# H2AR30.net
KiCad netlist of a schematic drawn in EAGLE
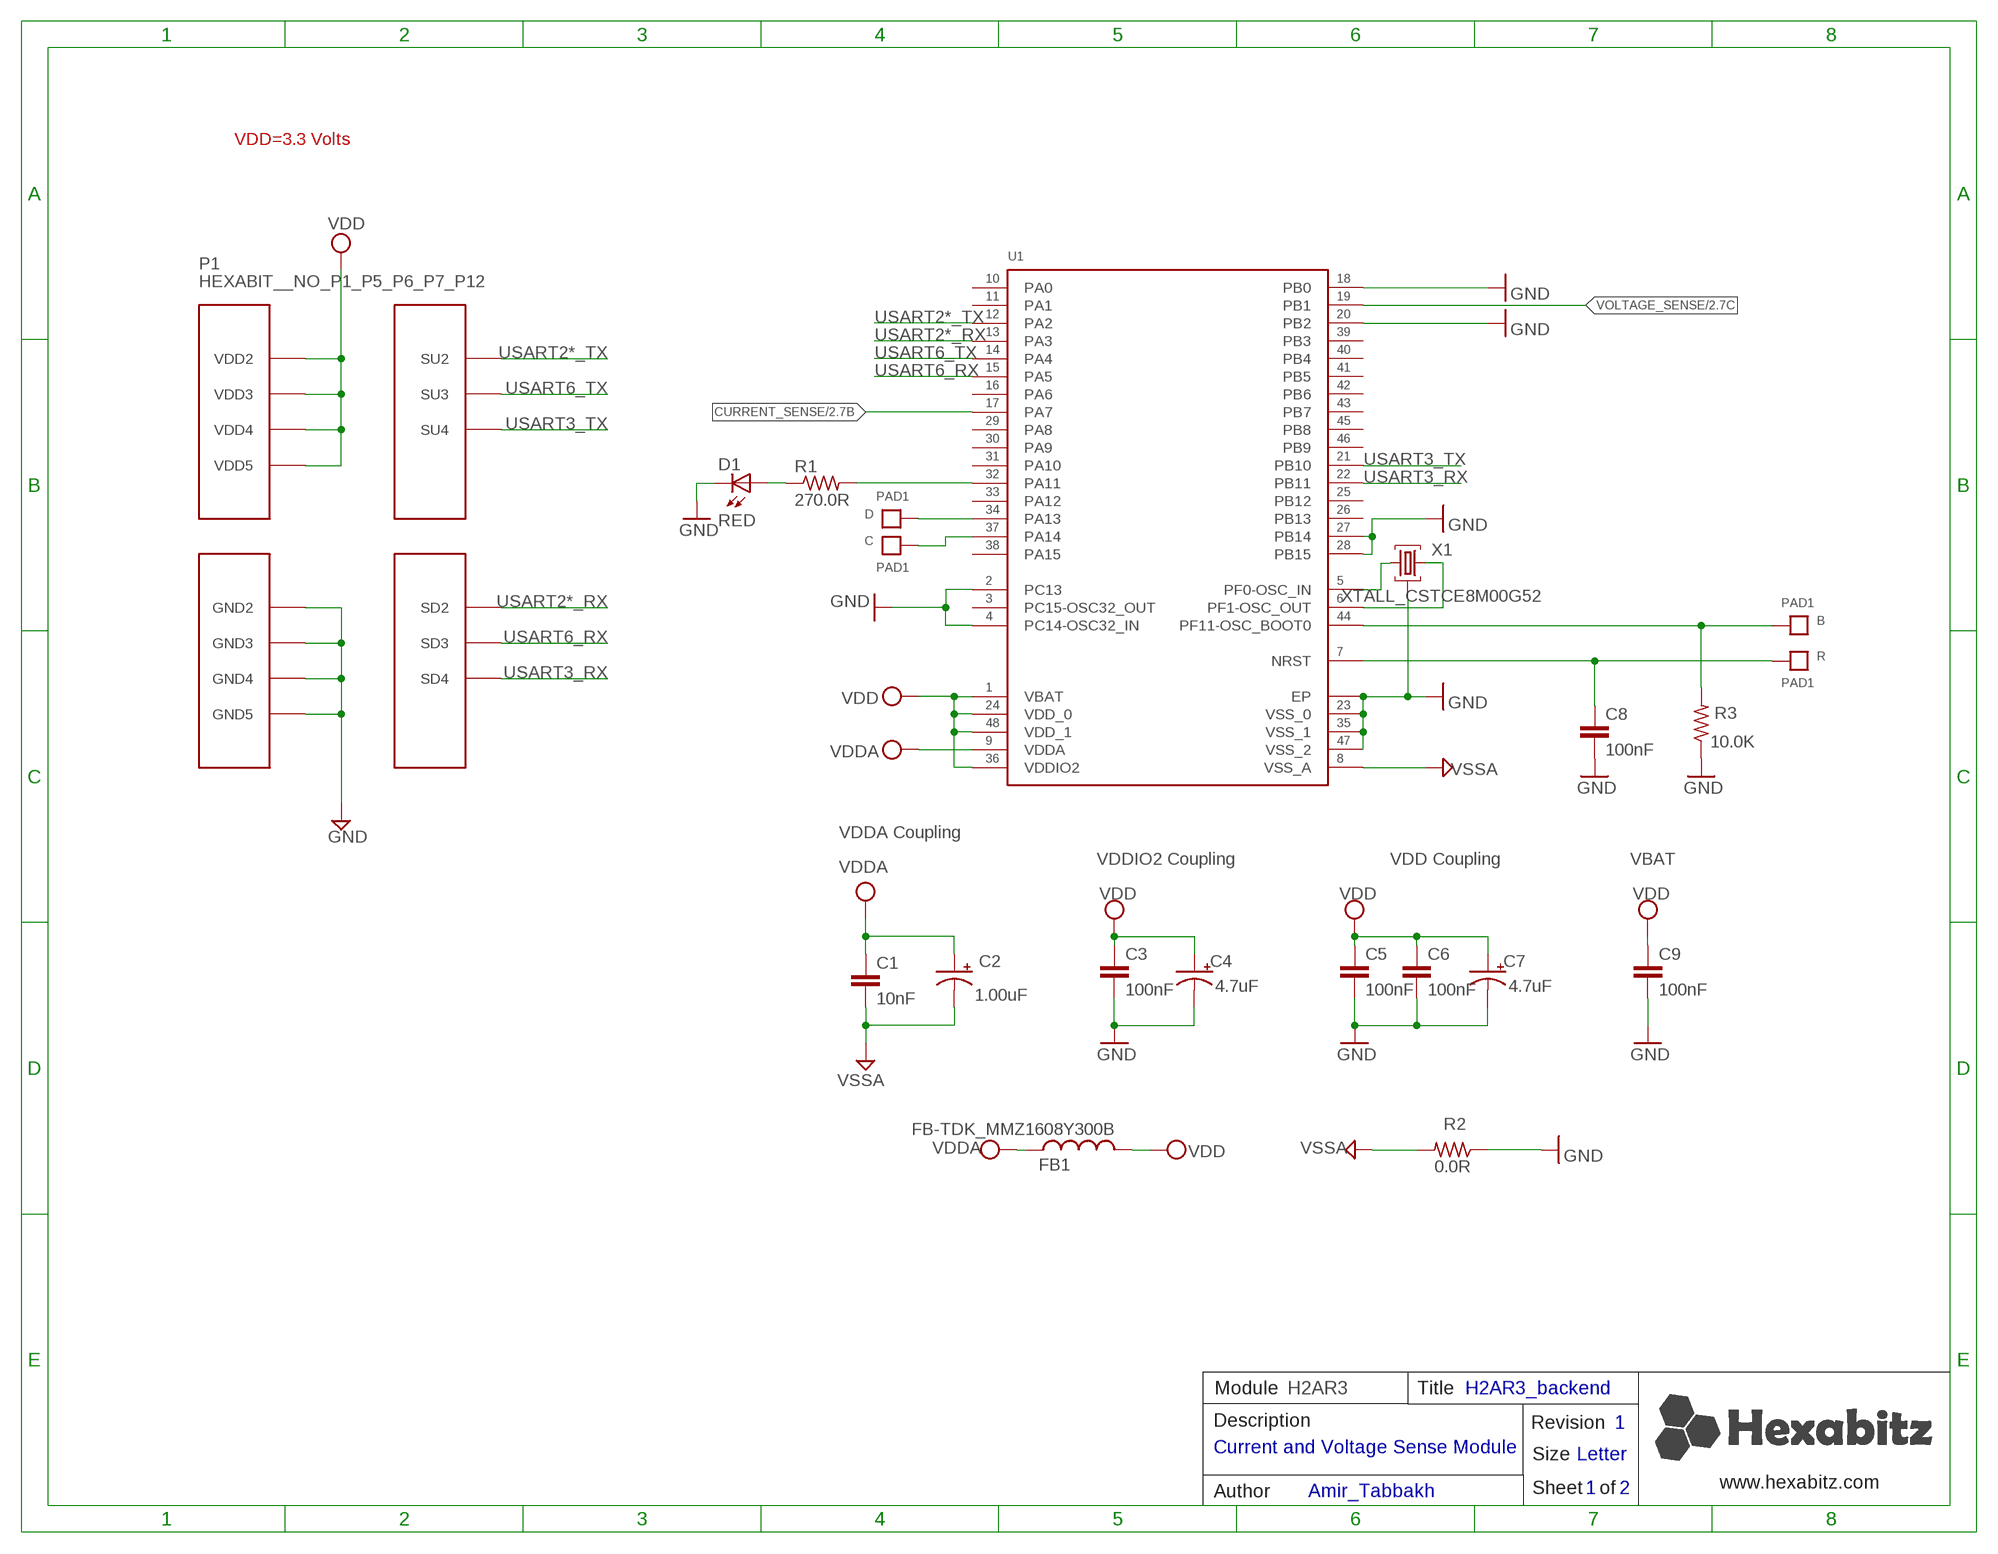
[diagram p0: schematic, sheet 1]
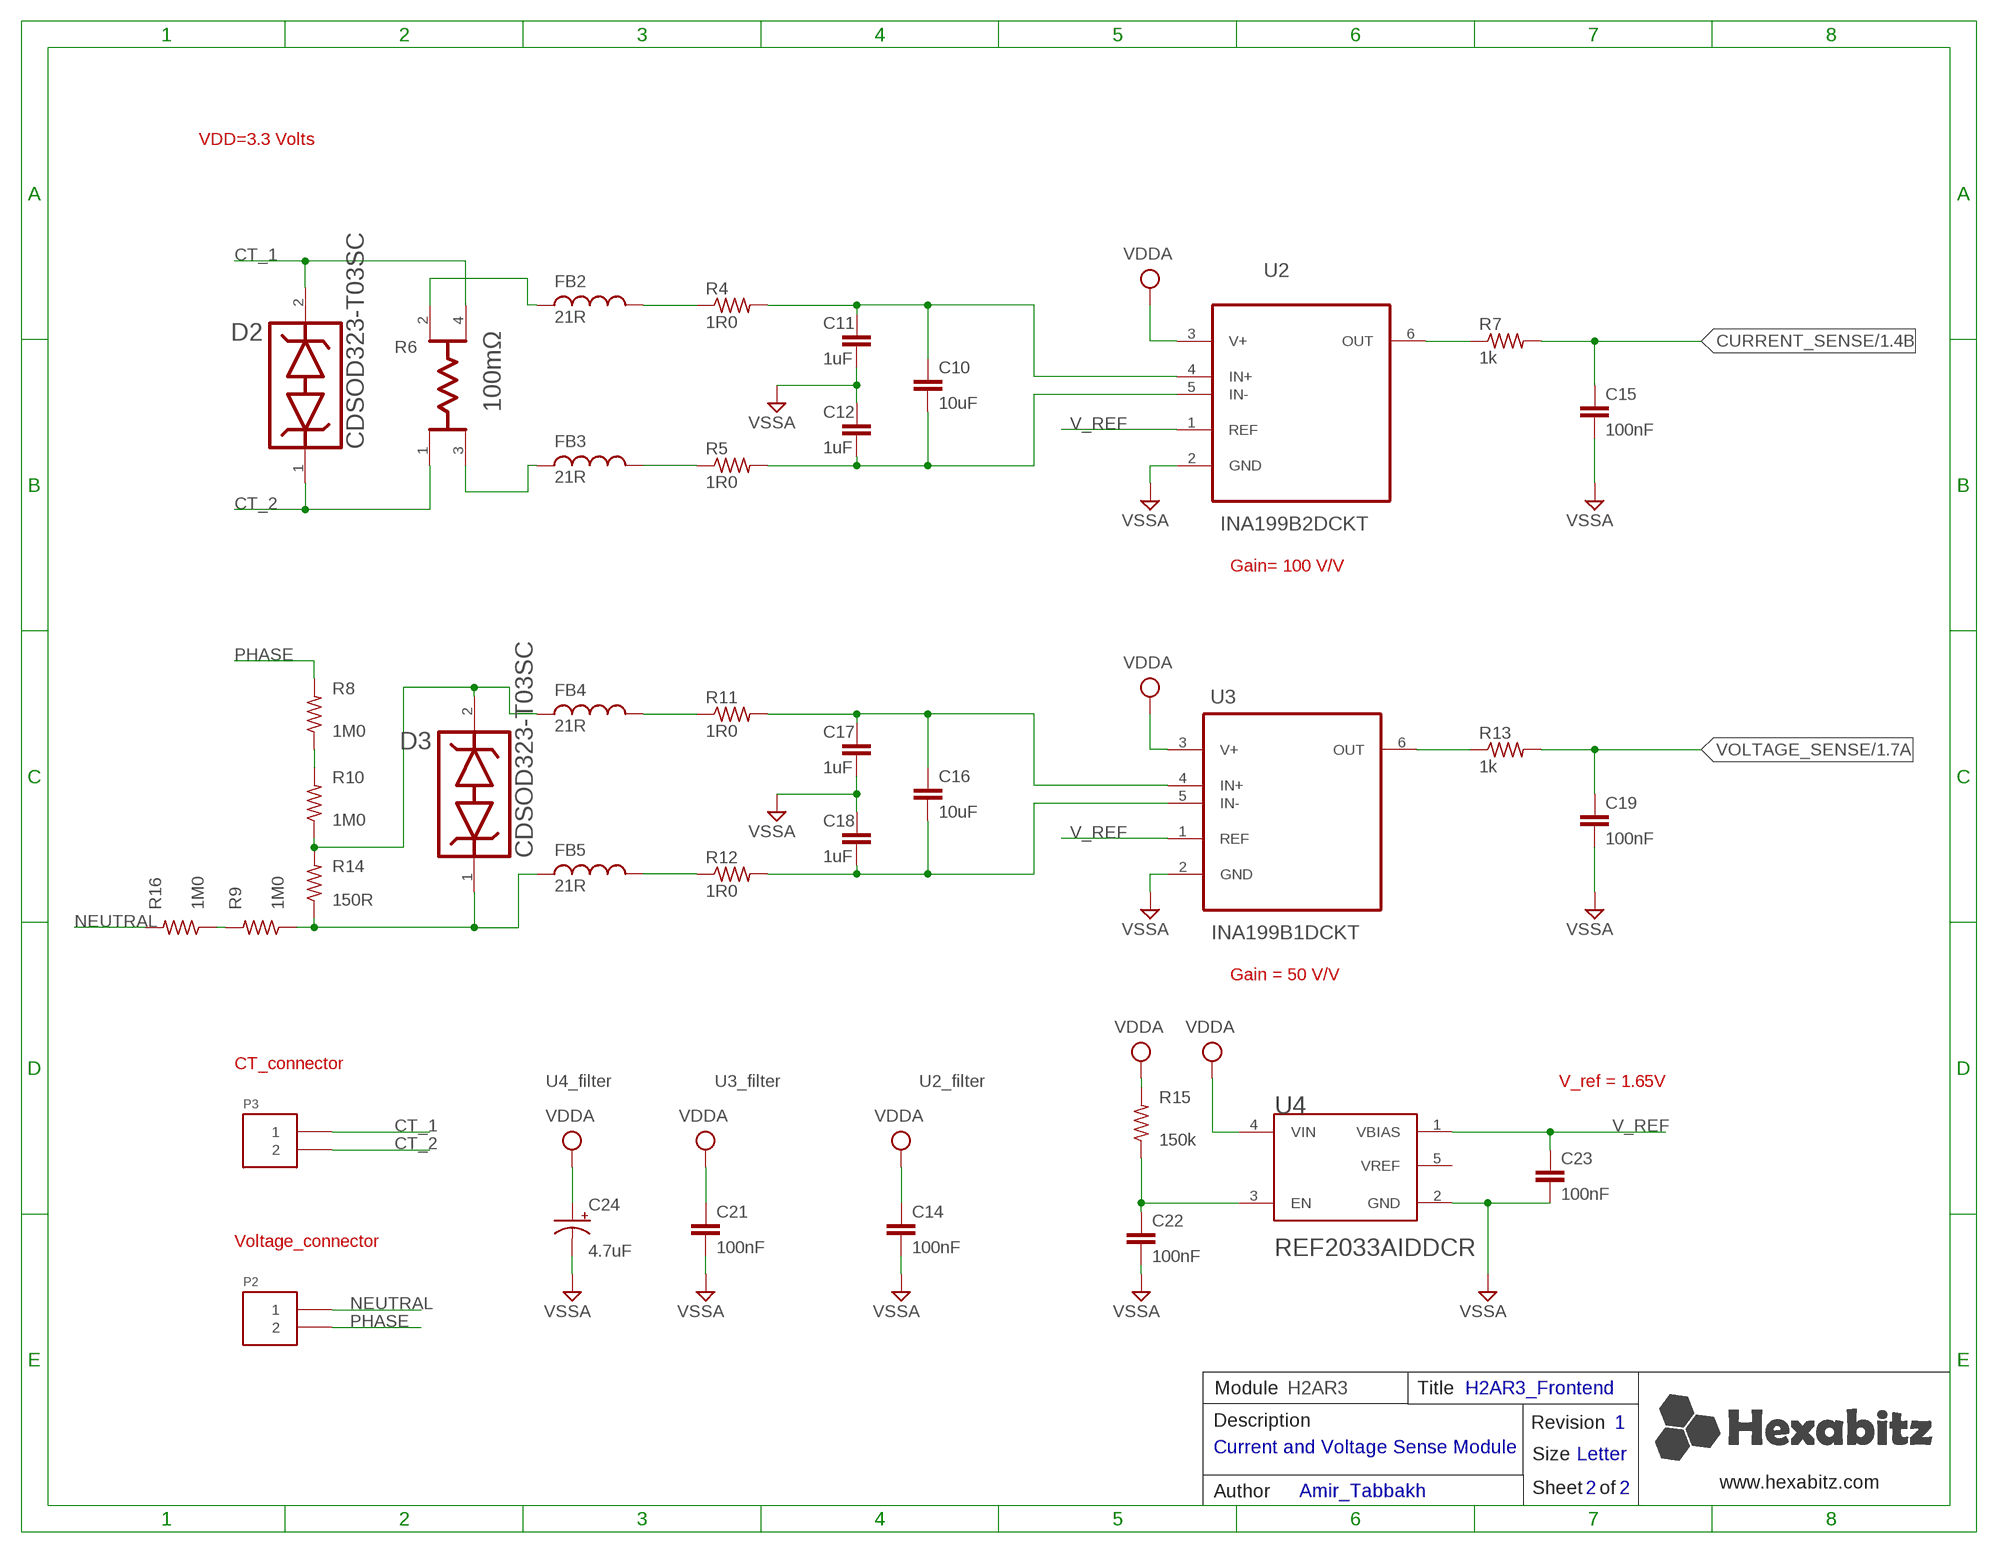
[diagram p1: schematic, sheet 2]

(export (version "E")
  (design (tool "Eeschema 10.0.6"))
  (components
    (comp (ref "C10")
      (value "10uF")
      (footprint "eagle-import:C-0603")
      (fields
        (field (name "CAPACITANCE") "10uF")
        (field (name "MFN") "KEMET")
        (field (name "MPN") "C0603C106M9PACTU")
        (field (name "OCTOPART_URL") "https://octopart.com/c0603c106m9pactu-kemet-8375727?r=sp")
        (field (name "VOLTAGE_RATING") "6.3v")
      )
      (libsource (lib "eagle-import") (part "C-0603"))
    )
    (comp (ref "C11")
      (value "1uF")
      (footprint "eagle-import:C-0603")
      (fields
        (field (name "CAPACITANCE") "1uF")
        (field (name "MFN") "KEMET")
        (field (name "MPN") "C0603C105K8RACTU")
        (field (name "OCTOPART_URL") "https://octopart.com/c0603c105k8ractu-kemet-12595642?r=sp")
        (field (name "TOLERANCE") "10%")
        (field (name "VOLTAGE_RATING") "10v")
      )
      (libsource (lib "eagle-import") (part "C-0603"))
    )
    (comp (ref "C12")
      (value "1uF")
      (footprint "eagle-import:C-0603")
      (fields
        (field (name "CAPACITANCE") "1uF")
        (field (name "MFN") "KEMET")
        (field (name "MPN") "C0603C105K8RACTU")
        (field (name "OCTOPART_URL") "https://octopart.com/c0603c105k8ractu-kemet-12595642?r=sp")
        (field (name "TOLERANCE") "10%")
        (field (name "VOLTAGE_RATING") "10v")
      )
      (libsource (lib "eagle-import") (part "C-0603"))
    )
    (comp (ref "C14")
      (value "100nF")
      (footprint "eagle-import:C-0603")
      (fields
        (field (name "CAPACITANCE") "100nF")
        (field (name "MFN") "KEMET")
        (field (name "MPN") "C0603C104K8RACTU")
        (field (name "OCTOPART_URL") "https://octopart.com/c0603c104k8ractu-kemet-145075?r=sp&s=9bS9ASSwSEqMCE9KBEQZ0g")
        (field (name "TOLERANCE") "10%")
        (field (name "VOLTAGE_RATING") "10V")
      )
      (libsource (lib "eagle-import") (part "C-0603"))
    )
    (comp (ref "C15")
      (value "100nF")
      (footprint "eagle-import:C-0603")
      (fields
        (field (name "CAPACITANCE") "100nF")
        (field (name "MFN") "KEMET")
        (field (name "MPN") "C0603C104K8RACTU")
        (field (name "OCTOPART_URL") "https://octopart.com/c0603c104k8ractu-kemet-145075?r=sp&s=9bS9ASSwSEqMCE9KBEQZ0g")
        (field (name "TOLERANCE") "10%")
        (field (name "VOLTAGE_RATING") "10V")
      )
      (libsource (lib "eagle-import") (part "C-0603"))
    )
    (comp (ref "C16")
      (value "10uF")
      (footprint "eagle-import:C-0603")
      (fields
        (field (name "CAPACITANCE") "10uF")
        (field (name "MFN") "KEMET")
        (field (name "MPN") "C0603C106M9PACTU")
        (field (name "OCTOPART_URL") "https://octopart.com/c0603c106m9pactu-kemet-8375727?r=sp")
        (field (name "TOLERANCE") "20%")
        (field (name "VOLTAGE_RATING") "6.3V")
      )
      (libsource (lib "eagle-import") (part "C-0603"))
    )
    (comp (ref "C17")
      (value "1uF")
      (footprint "eagle-import:C-0603")
      (fields
        (field (name "CAPACITANCE") "1uF")
        (field (name "MFN") "KEMET")
        (field (name "MPN") "C0603C105K8RACTU")
        (field (name "OCTOPART_URL") "https://octopart.com/c0603c105k8ractu-kemet-12595642?r=sp")
        (field (name "TOLERANCE") "10%")
        (field (name "VOLTAGE_RATING") "10v")
      )
      (libsource (lib "eagle-import") (part "C-0603"))
    )
    (comp (ref "C18")
      (value "1uF")
      (footprint "eagle-import:C-0603")
      (fields
        (field (name "CAPACITANCE") "1uF")
        (field (name "MFN") "KEMET")
        (field (name "MPN") "C0603C105K8RACTU")
        (field (name "OCTOPART_URL") "https://octopart.com/c0603c105k8ractu-kemet-12595642?r=sp")
        (field (name "TOLERANCE") "10%")
        (field (name "VOLTAGE_RATING") "10v")
      )
      (libsource (lib "eagle-import") (part "C-0603"))
    )
    (comp (ref "C19")
      (value "100nF")
      (footprint "eagle-import:C-0603")
      (fields
        (field (name "CAPACITANCE") "100nF")
        (field (name "MFN") "KEMET")
        (field (name "MPN") "C0603C104K8RACTU")
        (field (name "OCTOPART_URL") "https://octopart.com/c0603c104k8ractu-kemet-145075?r=sp&s=9bS9ASSwSEqMCE9KBEQZ0g")
        (field (name "TOLERANCE") "10%")
        (field (name "VOLTAGE_RATING") "10V")
      )
      (libsource (lib "eagle-import") (part "C-0603"))
    )
    (comp (ref "C21")
      (value "100nF")
      (footprint "eagle-import:C-0603")
      (fields
        (field (name "CAPACITANCE") "100nF")
        (field (name "MFN") "KEMET")
        (field (name "MPN") "C0603C104K8RACTU")
        (field (name "OCTOPART_URL") "https://octopart.com/c0603c104k8ractu-kemet-145075?r=sp&s=9bS9ASSwSEqMCE9KBEQZ0g")
        (field (name "TOLERANCE") "10%")
        (field (name "VOLTAGE_RATING") "10V")
      )
      (libsource (lib "eagle-import") (part "C-0603"))
    )
    (comp (ref "C22")
      (value "100nF")
      (footprint "eagle-import:C-0603")
      (fields
        (field (name "CAPACITANCE") "100nF")
        (field (name "MFN") "KEMET")
        (field (name "MPN") "C0603C104K8RACTU")
        (field (name "OCTOPART_URL") "https://octopart.com/c0603c104k8ractu-kemet-145075?r=sp&s=9bS9ASSwSEqMCE9KBEQZ0g")
        (field (name "TOLERANCE") "10%")
        (field (name "VOLTAGE_RATING") "10V")
      )
      (libsource (lib "eagle-import") (part "C-0603"))
    )
    (comp (ref "C23")
      (value "100nF")
      (footprint "eagle-import:C-0603")
      (fields
        (field (name "CAPACITANCE") "100nF")
        (field (name "MFN") "KEMET")
        (field (name "MPN") "C0603C104K8RACTU")
        (field (name "OCTOPART_URL") "https://octopart.com/c0603c104k8ractu-kemet-145075?r=sp&s=9bS9ASSwSEqMCE9KBEQZ0g")
        (field (name "TOLERANCE") "10%")
        (field (name "VOLTAGE_RATING") "10V")
      )
      (libsource (lib "eagle-import") (part "C-0603"))
    )
    (comp (ref "C24")
      (value "4.7uF")
      (footprint "eagle-import:C-0805-POL")
      (fields
        (field (name "CAPACITANCE") "4.7uF")
        (field (name "MFN") "Murata")
        (field (name "MPN") "GRM21BC81E475KA12L")
        (field (name "OCTOPART_URL") "https://octopart.com/grm21bc81e475ka12l-murata-10331911?r=sp&s=RY3qZSD8T6mG6TC9CHI5qQ")
        (field (name "TOLERANCE") "10%")
        (field (name "VOLTAGE_RATING") "25V")
      )
      (libsource (lib "eagle-import") (part "C-0805-POL"))
    )
    (comp (ref "D2")
      (value "BOURNS_CDSOD323-T03SCBOURNS_CDSOD323-T03SC_0_0")
      (footprint "eagle-import:BOURNS_CDSOD323-T03SC_0")
      (fields (field (name "MPN") "CDSOD323-T03SC"))
      (libsource (lib "eagle-import") (part "BOURNS_CDSOD323-T03SCBOURNS_CDSOD323-T03SC_0_0"))
    )
    (comp (ref "D3")
      (value "BOURNS_CDSOD323-T03SCBOURNS_CDSOD323-T03SC_0_0")
      (footprint "eagle-import:BOURNS_CDSOD323-T03SC_0")
      (fields (field (name "MPN") "CDSOD323-T03SC"))
      (libsource (lib "eagle-import") (part "BOURNS_CDSOD323-T03SCBOURNS_CDSOD323-T03SC_0_0"))
    )
    (comp (ref "FB2")
      (value "21R")
      (footprint "eagle-import:FB-0805")
      (fields
        (field (name "MFN") "Taiyo Yuden")
        (field (name "MPN") "FBMJ2125HM210NT")
        (field (name "OCTOPART_URL") "https://octopart.com/fbmj2125hm210nt-taiyo+yuden-368424?r=sp")
      )
      (libsource (lib "eagle-import") (part "FB-0805"))
    )
    (comp (ref "FB3")
      (value "21R")
      (footprint "eagle-import:FB-0805")
      (fields
        (field (name "MFN") "Taiyo Yuden")
        (field (name "MPN") "FBMJ2125HM210NT")
        (field (name "OCTOPART_URL") "https://octopart.com/fbmj2125hm210nt-taiyo+yuden-368424?r=sp")
      )
      (libsource (lib "eagle-import") (part "FB-0805"))
    )
    (comp (ref "FB4")
      (value "21R")
      (footprint "eagle-import:FB-0805")
      (fields
        (field (name "MFN") "Taiyo Yuden")
        (field (name "MPN") "FBMJ2125HM210NT")
        (field (name "OCTOPART_URL") "https://octopart.com/fbmj2125hm210nt-taiyo+yuden-368424?r=sp")
      )
      (libsource (lib "eagle-import") (part "FB-0805"))
    )
    (comp (ref "FB5")
      (value "21R")
      (footprint "eagle-import:FB-0805")
      (fields
        (field (name "MFN") "Taiyo Yuden")
        (field (name "MPN") "FBMJ2125HM210NT")
        (field (name "OCTOPART_URL") "https://octopart.com/fbmj2125hm210nt-taiyo+yuden-368424?r=sp")
      )
      (libsource (lib "eagle-import") (part "FB-0805"))
    )
    (comp (ref "P2")
      (value "1546111-2")
      (footprint "eagle-import:1546111-2")
      (libsource (lib "eagle-import") (part "1546111-2"))
    )
    (comp (ref "P3")
      (value "1546111-2")
      (footprint "eagle-import:1546111-2")
      (libsource (lib "eagle-import") (part "1546111-2"))
    )
    (comp (ref "R4")
      (value "1R0")
      (footprint "eagle-import:R-0603")
      (fields
        (field (name "MFN") "Vishay")
        (field (name "MPN") "CRCW06031R00FKEA")
        (field (name "OCTOPART_URL") "https://octopart.com/crcw06031r00fkea-vishay-39713722?r=sp&s=biXSlGylTBiwPOCcABx_kA")
        (field (name "RESISTANCE") "1")
        (field (name "TOLERANCE") "1%")
      )
      (libsource (lib "eagle-import") (part "R-0603"))
    )
    (comp (ref "R5")
      (value "1R0")
      (footprint "eagle-import:R-0603")
      (fields
        (field (name "MFN") "Vishay")
        (field (name "MPN") "CRCW06031R00FKEA")
        (field (name "OCTOPART_URL") "https://octopart.com/crcw06031r00fkea-vishay-39713722?r=sp&s=biXSlGylTBiwPOCcABx_kA")
        (field (name "RESISTANCE") "1")
        (field (name "TOLERANCE") "1%")
      )
      (libsource (lib "eagle-import") (part "R-0603"))
    )
    (comp (ref "R6")
      (value "VISHAY_Y14870R10000B9RVISHAY_Y14870R10000B9R_0_0")
      (footprint "eagle-import:VISHAY_Y14870R10000B9R_0")
      (fields (field (name "MPN") "Y14870R10000B9R"))
      (libsource (lib "eagle-import") (part "VISHAY_Y14870R10000B9RVISHAY_Y14870R10000B9R_0_0"))
    )
    (comp (ref "R7")
      (value "1k")
      (footprint "eagle-import:R-0603")
      (fields
        (field (name "MFN") "Yageo")
        (field (name "MPN") "RC0603JR-071KL")
        (field (name "OCTOPART_URL") "https://octopart.com/rc0603jr-071kl-yageo-55402888?r=sp")
        (field (name "RESISTANCE") "1K")
        (field (name "TOLERANCE") "5%")
      )
      (libsource (lib "eagle-import") (part "R-0603"))
    )
    (comp (ref "R8")
      (value "1M0")
      (footprint "eagle-import:R1206")
      (fields
        (field (name "MPN") "RNCF2512BTE1M10")
        (field (name "MFN") "Yageo")
        (field (name "MPN_1") "RT1206BRD071ML")
        (field (name "OCTOPART_URL") "https://octopart.com/rt1206brd071ml-yageo-1262221?r=sp")
      )
      (libsource (lib "eagle-import") (part "R_1206R1206"))
    )
    (comp (ref "R9")
      (value "1M0")
      (footprint "eagle-import:R1206")
      (fields
        (field (name "MPN") "RNCF2512BTE1M10")
        (field (name "MFN") "Yageo")
        (field (name "MPN_1") "RT1206BRD071ML")
        (field (name "OCTOPART_URL") "https://octopart.com/rt1206brd071ml-yageo-1262221?r=sp")
      )
      (libsource (lib "eagle-import") (part "R_1206R1206"))
    )
    (comp (ref "R10")
      (value "1M0")
      (footprint "eagle-import:R1206")
      (fields
        (field (name "MPN") "RNCF2512BTE1M10")
        (field (name "MFN") "Yageo")
        (field (name "MPN_1") "RT1206BRD071ML")
        (field (name "OCTOPART_URL") "https://octopart.com/rt1206brd071ml-yageo-1262221?r=sp")
      )
      (libsource (lib "eagle-import") (part "R_1206R1206"))
    )
    (comp (ref "R11")
      (value "1R0")
      (footprint "eagle-import:R-0603")
      (fields
        (field (name "MFN") "Vishay")
        (field (name "MPN") "CRCW06031R00FKEA")
        (field (name "OCTOPART_URL") "https://octopart.com/crcw06031r00fkea-vishay-39713722?r=sp&s=biXSlGylTBiwPOCcABx_kA")
        (field (name "RESISTANCE") "1")
        (field (name "TOLERANCE") "1%")
      )
      (libsource (lib "eagle-import") (part "R-0603"))
    )
    (comp (ref "R12")
      (value "1R0")
      (footprint "eagle-import:R-0603")
      (fields
        (field (name "MFN") "Vishay")
        (field (name "MPN") "CRCW06031R00FKEA")
        (field (name "OCTOPART_URL") "https://octopart.com/crcw06031r00fkea-vishay-39713722?r=sp&s=biXSlGylTBiwPOCcABx_kA")
        (field (name "RESISTANCE") "1")
        (field (name "TOLERANCE") "1%")
      )
      (libsource (lib "eagle-import") (part "R-0603"))
    )
    (comp (ref "R13")
      (value "1k")
      (footprint "eagle-import:R-0603")
      (fields
        (field (name "MFN") "Yageo")
        (field (name "MPN") "RC0603JR-071KL")
        (field (name "OCTOPART_URL") "https://octopart.com/rc0603jr-071kl-yageo-55402888?r=sp")
        (field (name "RESISTANCE") "1K")
        (field (name "TOLERANCE") "5%")
      )
      (libsource (lib "eagle-import") (part "R-0603"))
    )
    (comp (ref "R14")
      (value "150R")
      (footprint "eagle-import:R1206")
      (fields
        (field (name "MPN") "RNCF2512BTE1M10")
        (field (name "MFN") "Panasonic")
        (field (name "MPN_1") "ERA-8AEB151V")
        (field (name "OCTOPART_URL") "https://octopart.com/era-8aeb151v-panasonic-55477439?r=sp")
      )
      (libsource (lib "eagle-import") (part "R_1206R1206"))
    )
    (comp (ref "R15")
      (value "150k")
      (footprint "eagle-import:R-0603")
      (fields
        (field (name "MFN") "Vishay")
        (field (name "MPN") "CRCW0603150KFKEA")
        (field (name "OCTOPART_URL") "https://octopart.com/crcw0603150kfkea-vishay-39455816?r=sp")
        (field (name "RESISTANCE") "150K")
        (field (name "TOLERANCE") "1%")
      )
      (libsource (lib "eagle-import") (part "R-0603"))
    )
    (comp (ref "R16")
      (value "1M0")
      (footprint "eagle-import:R1206")
      (fields
        (field (name "MPN") "RNCF2512BTE1M10")
        (field (name "MFN") "Yageo")
        (field (name "MPN_1") "RT1206BRD071ML")
        (field (name "OCTOPART_URL") "https://octopart.com/rt1206brd071ml-yageo-1262221?r=sp")
      )
      (libsource (lib "eagle-import") (part "R_1206R1206"))
    )
    (comp (ref "U2")
      (value "INA199B2DCKT")
      (footprint "eagle-import:SOT65P210X110-6N")
      (libsource (lib "eagle-import") (part "INA199B2DCKT"))
    )
    (comp (ref "U3")
      (value "INA199B1DCKT")
      (footprint "eagle-import:SOT65P210X110-6N")
      (libsource (lib "eagle-import") (part "INA199B1DCKT"))
    )
    (comp (ref "U4")
      (value "TEXAS_INSTRUMENTS_REF2033AIDDCRTEXAS_INSTRUMENTS_REF2033AIDDCR_0_2")
      (footprint "eagle-import:TEXAS_INSTRUMENTS_REF2033AIDDCR_2")
      (fields (field (name "MPN") "REF2033AIDDCR"))
      (libsource (lib "eagle-import") (part "TEXAS_INSTRUMENTS_REF2033AIDDCRTEXAS_INSTRUMENTS_REF2033AIDDCR_0_2"))
    )
    (comp (ref "B")
      (value "PAD1")
      (footprint "eagle-import:PAD1")
      (libsource (lib "eagle-import") (part "PAD1"))
    )
    (comp (ref "C")
      (value "PAD1")
      (footprint "eagle-import:PAD1")
      (libsource (lib "eagle-import") (part "PAD1"))
    )
    (comp (ref "C1")
      (value "10nF")
      (footprint "eagle-import:C-0603")
      (fields
        (field (name "CAPACITANCE") "10nF")
        (field (name "MFN") "KEMET")
        (field (name "MPN") "C0603C103K5RACTU")
        (field (name "OCTOPART_URL") "https://octopart.com/c0603c103k5ractu-kemet-133094?r=sp&s=R_iPBxLnSmGqhkU2rIMFpg")
        (field (name "TOLERANCE") "10%")
        (field (name "VOLTAGE_RATING") "50V")
      )
      (libsource (lib "eagle-import") (part "C-0603"))
    )
    (comp (ref "C2")
      (value "1.00uF")
      (footprint "eagle-import:C-0805-POL")
      (fields
        (field (name "CAPACITANCE") "1.00uF")
        (field (name "MFN") "Yageo")
        (field (name "MPN") "CC0805KKX7R7BB105")
        (field (name "OCTOPART_URL") "https://octopart.com/cc0805kkx7r7bb105-yageo-8376555?r=sp&s=YKl1wwtkROau_X5nniH2ig")
        (field (name "TOLERANCE") "10%")
        (field (name "VOLTAGE_RATING") "16V")
      )
      (libsource (lib "eagle-import") (part "C-0805-POL"))
    )
    (comp (ref "C3")
      (value "100nF")
      (footprint "eagle-import:C-0603")
      (fields
        (field (name "CAPACITANCE") "100nF")
        (field (name "MFN") "KEMET")
        (field (name "MPN") "C0603C104K8RACTU")
        (field (name "OCTOPART_URL") "https://octopart.com/c0603c104k8ractu-kemet-145075?r=sp&s=9bS9ASSwSEqMCE9KBEQZ0g")
        (field (name "TOLERANCE") "10%")
        (field (name "VOLTAGE_RATING") "10V")
      )
      (libsource (lib "eagle-import") (part "C-0603"))
    )
    (comp (ref "C4")
      (value "4.7uF")
      (footprint "eagle-import:C-0805-POL")
      (fields
        (field (name "CAPACITANCE") "4.7uF")
        (field (name "MFN") "Murata")
        (field (name "MPN") "GRM21BC81E475KA12L")
        (field (name "OCTOPART_URL") "https://octopart.com/grm21bc81e475ka12l-murata-10331911?r=sp&s=RY3qZSD8T6mG6TC9CHI5qQ")
        (field (name "TOLERANCE") "10%")
        (field (name "VOLTAGE_RATING") "25V")
      )
      (libsource (lib "eagle-import") (part "C-0805-POL"))
    )
    (comp (ref "C5")
      (value "100nF")
      (footprint "eagle-import:C-0603")
      (fields
        (field (name "CAPACITANCE") "100nF")
        (field (name "MFN") "KEMET")
        (field (name "MPN") "C0603C104K8RACTU")
        (field (name "OCTOPART_URL") "https://octopart.com/c0603c104k8ractu-kemet-145075?r=sp&s=9bS9ASSwSEqMCE9KBEQZ0g")
        (field (name "TOLERANCE") "10%")
        (field (name "VOLTAGE_RATING") "10")
      )
      (libsource (lib "eagle-import") (part "C-0603"))
    )
    (comp (ref "C6")
      (value "100nF")
      (footprint "eagle-import:C-0603")
      (fields
        (field (name "CAPACITANCE") "100nF")
        (field (name "MFN") "KEMET")
        (field (name "MPN") "C0603C104K8RACTU")
        (field (name "OCTOPART_URL") "https://octopart.com/c0603c104k8ractu-kemet-145075?r=sp&s=9bS9ASSwSEqMCE9KBEQZ0g")
        (field (name "TOLERANCE") "10%")
        (field (name "VOLTAGE_RATING") "10V")
      )
      (libsource (lib "eagle-import") (part "C-0603"))
    )
    (comp (ref "C7")
      (value "4.7uF")
      (footprint "eagle-import:C-0805-POL")
      (fields
        (field (name "CAPACITANCE") "4.7uF")
        (field (name "MFN") "Murata")
        (field (name "MPN") "GRM21BC81E475KA12L")
        (field (name "OCTOPART_URL") "https://octopart.com/grm21bc81e475ka12l-murata-10331911?r=sp&s=RY3qZSD8T6mG6TC9CHI5qQ")
        (field (name "TOLERANCE") "10%")
        (field (name "VOLTAGE_RATING") "25V")
      )
      (libsource (lib "eagle-import") (part "C-0805-POL"))
    )
    (comp (ref "C8")
      (value "100nF")
      (footprint "eagle-import:C-0603")
      (fields
        (field (name "CAPACITANCE") "100nF")
        (field (name "MFN") "KEMET")
        (field (name "MPN") "C0603C104K8RACTU")
        (field (name "OCTOPART_URL") "https://octopart.com/c0603c104k8ractu-kemet-145075?r=sp&s=9bS9ASSwSEqMCE9KBEQZ0g")
        (field (name "TOLERANCE") "10%")
        (field (name "VOLTAGE_RATING") "10V")
      )
      (libsource (lib "eagle-import") (part "C-0603"))
    )
    (comp (ref "C9")
      (value "100nF")
      (footprint "eagle-import:C-0603")
      (fields
        (field (name "CAPACITANCE") "100nF")
        (field (name "MFN") "KEMET")
        (field (name "MPN") "C0603C104K8RACTU")
        (field (name "OCTOPART_URL") "https://octopart.com/c0603c104k8ractu-kemet-145075?r=sp&s=9bS9ASSwSEqMCE9KBEQZ0g")
        (field (name "TOLERANCE") "10V")
        (field (name "VOLTAGE_RATING") "10%")
      )
      (libsource (lib "eagle-import") (part "C-0603"))
    )
    (comp (ref "D")
      (value "PAD1")
      (footprint "eagle-import:PAD1")
      (libsource (lib "eagle-import") (part "PAD1"))
    )
    (comp (ref "D1")
      (value "RED")
      (footprint "eagle-import:VLMS1300-GS08")
      (fields
        (field (name "MPN") "VLMS1300-GS08")
        (field (name "MFN") "Vishay")
        (field (name "MPN_1") "VLMS1300-GS08")
        (field (name "OCTOPART_URL") "https://octopart.com/vlms1300-gs08-vishay-21709201?r=sp&s=_gcP4_q8T1SC6PJQPTQ9yA")
      )
      (libsource (lib "eagle-import") (part "VLMS1300-GS08"))
    )
    (comp (ref "FB1")
      (value "FB-TDK_MMZ1608Y300B")
      (footprint "eagle-import:FB-TDK_MMZ1608Y300B")
      (fields
        (field (name "MFN") "TDK ")
        (field (name "MPN") "MMZ1608Y300B")
        (field (name "OCTOPART_URL") "https://octopart.com/mmz1608y300b-tdk-368280?r=sp&s=cd9_2ZEqQ9q9UNBuQgHAiA")
      )
      (libsource (lib "eagle-import") (part "FB-TDK_MMZ1608Y300B"))
    )
    (comp (ref "P1")
      (value "HEXABIT__NO_P1_P5_P6_P7_P12")
      (footprint "eagle-import:HEXABIT_17.32_NO_P1_P6_P5_P7_P12")
      (libsource (lib "eagle-import") (part "HEXABIT_?_NO_P1_P5_P6_P7_P12"))
    )
    (comp (ref "R")
      (value "PAD1")
      (footprint "eagle-import:PAD1")
      (libsource (lib "eagle-import") (part "PAD1"))
    )
    (comp (ref "R1")
      (value "270.0R")
      (footprint "eagle-import:R-0603")
      (fields
        (field (name "MFN") "Yageo")
        (field (name "MPN") "RC0603FR-07270RL")
        (field (name "OCTOPART_URL") "https://octopart.com/search?q=RC0603FR-07270RL&start=0")
        (field (name "RESISTANCE") "270.0 Ohm")
        (field (name "TOLERANCE") "5%")
      )
      (libsource (lib "eagle-import") (part "R-0603"))
    )
    (comp (ref "R2")
      (value "0.0R")
      (footprint "eagle-import:R-0603")
      (fields
        (field (name "MFN") "Yageo")
        (field (name "MPN") "RC0603JR-070RL")
        (field (name "OCTOPART_URL") "https://octopart.com/rc0603jr-070rl-yageo-1241539?r=sp&s=X2NteqRjRNWrnx42Y0aliA")
        (field (name "RESISTANCE") "0.0 Ohm")
      )
      (libsource (lib "eagle-import") (part "R-0603"))
    )
    (comp (ref "R3")
      (value "10.0K")
      (footprint "eagle-import:R-0603")
      (fields
        (field (name "MFN") "Yageo")
        (field (name "MPN") "RC0603JR-0710KL")
        (field (name "OCTOPART_URL") "https://octopart.com/search?q=RC0603JR-0710KL&start=0")
        (field (name "RESISTANCE") "10.0K Ohm")
        (field (name "TOLERANCE") "5%")
      )
      (libsource (lib "eagle-import") (part "R-0603"))
    )
    (comp (ref "U1")
      (value "STM32F091CBU6")
      (footprint "eagle-import:STM32F091CBU6")
      (libsource (lib "eagle-import") (part "STM32F091CBU6"))
    )
    (comp (ref "X1")
      (value "XTALL_CSTCE8M00G52")
      (footprint "eagle-import:XTALL_CSTCE8M00G52")
      (fields (field (name "MPN") "CSTCE8M00G52Z-R0"))
      (libsource (lib "eagle-import") (part "XTALL_CSTCE8M00G52"))
    )
  )
  (nets
    (net (code "1") (name "AGND") (class "Default")
      (node (ref "C1") (pin "2") (pinfunction "2_2") (pintype "passive"))
      (node (ref "C11") (pin "1") (pinfunction "1_1") (pintype "passive"))
      (node (ref "C12") (pin "2") (pinfunction "2_2") (pintype "passive"))
      (node (ref "C14") (pin "2") (pinfunction "2_2") (pintype "passive"))
      (node (ref "C15") (pin "2") (pinfunction "2_2") (pintype "passive"))
      (node (ref "C17") (pin "1") (pinfunction "1_1") (pintype "passive"))
      (node (ref "C18") (pin "2") (pinfunction "2_2") (pintype "passive"))
      (node (ref "C19") (pin "2") (pinfunction "2_2") (pintype "passive"))
      (node (ref "C2") (pin "2") (pinfunction "-_2") (pintype "passive"))
      (node (ref "C21") (pin "2") (pinfunction "2_2") (pintype "passive"))
      (node (ref "C22") (pin "2") (pinfunction "2_2") (pintype "passive"))
      (node (ref "C23") (pin "2") (pinfunction "2_2") (pintype "passive"))
      (node (ref "C24") (pin "2") (pinfunction "-_2") (pintype "passive"))
      (node (ref "R2") (pin "2") (pinfunction "2_2") (pintype "passive"))
      (node (ref "U1") (pin "P$8") (pinfunction "VSS_A_P$8") (pintype "power_in"))
      (node (ref "U2") (pin "2") (pinfunction "GND_2") (pintype "passive"))
      (node (ref "U3") (pin "2") (pinfunction "GND_2") (pintype "passive"))
      (node (ref "U4") (pin "2") (pinfunction "GND_2") (pintype "power_in"))
    )
    (net (code "2") (name "CT_1") (class "Default")
      (node (ref "D2") (pin "2") (pinfunction "2_2") (pintype "bidirectional"))
      (node (ref "P3") (pin "1") (pinfunction "1_1") (pintype "power_in"))
      (node (ref "R6") (pin "4") (pinfunction "I2_4") (pintype "passive"))
    )
    (net (code "3") (name "CT_2") (class "Default")
      (node (ref "D2") (pin "1") (pinfunction "1_1") (pintype "bidirectional"))
      (node (ref "P3") (pin "2") (pinfunction "2_2") (pintype "power_in"))
      (node (ref "R6") (pin "1") (pinfunction "I1_1") (pintype "passive"))
    )
    (net (code "4") (name "CURRENT_SENSE") (class "Default")
      (node (ref "C15") (pin "1") (pinfunction "1_1") (pintype "passive"))
      (node (ref "R7") (pin "2") (pinfunction "2_2") (pintype "passive"))
      (node (ref "U1") (pin "P$17") (pinfunction "PA7_P$17") (pintype "bidirectional"))
    )
    (net (code "5") (name "GND") (class "Default")
      (node (ref "C3") (pin "2") (pinfunction "2_2") (pintype "passive"))
      (node (ref "C4") (pin "2") (pinfunction "-_2") (pintype "passive"))
      (node (ref "C5") (pin "2") (pinfunction "2_2") (pintype "passive"))
      (node (ref "C6") (pin "2") (pinfunction "2_2") (pintype "passive"))
      (node (ref "C7") (pin "2") (pinfunction "-_2") (pintype "passive"))
      (node (ref "C8") (pin "2") (pinfunction "2_2") (pintype "passive"))
      (node (ref "C9") (pin "2") (pinfunction "2_2") (pintype "passive"))
      (node (ref "D1") (pin "C") (pinfunction "C_C") (pintype "passive"))
      (node (ref "P1") (pin "PAD_PD10") (pinfunction "GND4_PAD_PD10") (pintype "power_in"))
      (node (ref "P1") (pin "PAD_PD11") (pinfunction "GND5_PAD_PD11") (pintype "power_in"))
      (node (ref "P1") (pin "PAD_PD8") (pinfunction "GND2_PAD_PD8") (pintype "power_in"))
      (node (ref "P1") (pin "PAD_PD9") (pinfunction "GND3_PAD_PD9") (pintype "power_in"))
      (node (ref "R2") (pin "1") (pinfunction "1_1") (pintype "passive"))
      (node (ref "R3") (pin "1") (pinfunction "1_1") (pintype "passive"))
      (node (ref "U1") (pin "EP") (pinfunction "EP_EP") (pintype "power_in"))
      (node (ref "U1") (pin "P$18") (pinfunction "PB0_P$18") (pintype "bidirectional"))
      (node (ref "U1") (pin "P$2") (pinfunction "PC13_P$2") (pintype "bidirectional"))
      (node (ref "U1") (pin "P$20") (pinfunction "PB2_P$20") (pintype "bidirectional"))
      (node (ref "U1") (pin "P$23") (pinfunction "VSS_0_P$23") (pintype "power_in"))
      (node (ref "U1") (pin "P$27") (pinfunction "PB14_P$27") (pintype "bidirectional"))
      (node (ref "U1") (pin "P$28") (pinfunction "PB15_P$28") (pintype "bidirectional"))
      (node (ref "U1") (pin "P$3") (pinfunction "PC14-OSC32_IN_P$3") (pintype "bidirectional"))
      (node (ref "U1") (pin "P$35") (pinfunction "VSS_1_P$35") (pintype "power_in"))
      (node (ref "U1") (pin "P$47") (pinfunction "VSS_2_P$47") (pintype "power_in"))
      (node (ref "X1") (pin "P$2") (pinfunction "2_P$2") (pintype "passive"))
    )
    (net (code "6") (name "NEUTRAL") (class "Default")
      (node (ref "P2") (pin "1") (pinfunction "1_1") (pintype "power_in"))
      (node (ref "R16") (pin "2") (pinfunction "2_2") (pintype "passive"))
    )
    (net (code "7") (name "Net-(D1-PadA)") (class "Default")
      (node (ref "D1") (pin "A") (pinfunction "A_A") (pintype "passive"))
      (node (ref "R1") (pin "1") (pinfunction "1_1") (pintype "passive"))
    )
    (net (code "8") (name "Net-(D3-Pad1)") (class "Default")
      (node (ref "D3") (pin "1") (pinfunction "1_1") (pintype "bidirectional"))
      (node (ref "FB5") (pin "1") (pinfunction "1_1") (pintype "passive"))
      (node (ref "R14") (pin "1") (pinfunction "1_1") (pintype "passive"))
      (node (ref "R9") (pin "1") (pinfunction "1_1") (pintype "passive"))
    )
    (net (code "9") (name "Net-(D3-Pad2)") (class "Default")
      (node (ref "D3") (pin "2") (pinfunction "2_2") (pintype "bidirectional"))
      (node (ref "FB4") (pin "1") (pinfunction "1_1") (pintype "passive"))
      (node (ref "R10") (pin "1") (pinfunction "1_1") (pintype "passive"))
      (node (ref "R14") (pin "2") (pinfunction "2_2") (pintype "passive"))
    )
    (net (code "10") (name "Net-(FB2-Pad2)") (class "Default")
      (node (ref "FB2") (pin "2") (pinfunction "2_2") (pintype "passive"))
      (node (ref "R4") (pin "1") (pinfunction "1_1") (pintype "passive"))
    )
    (net (code "11") (name "Net-(FB3-Pad2)") (class "Default")
      (node (ref "FB3") (pin "2") (pinfunction "2_2") (pintype "passive"))
      (node (ref "R5") (pin "1") (pinfunction "1_1") (pintype "passive"))
    )
    (net (code "12") (name "Net-(FB4-Pad2)") (class "Default")
      (node (ref "FB4") (pin "2") (pinfunction "2_2") (pintype "passive"))
      (node (ref "R11") (pin "1") (pinfunction "1_1") (pintype "passive"))
    )
    (net (code "13") (name "Net-(FB5-Pad2)") (class "Default")
      (node (ref "FB5") (pin "2") (pinfunction "2_2") (pintype "passive"))
      (node (ref "R12") (pin "1") (pinfunction "1_1") (pintype "passive"))
    )
    (net (code "14") (name "Net-(R6-E1)") (class "Default")
      (node (ref "FB3") (pin "1") (pinfunction "1_1") (pintype "passive"))
      (node (ref "R6") (pin "3") (pinfunction "E1_3") (pintype "passive"))
    )
    (net (code "15") (name "Net-(R6-E2)") (class "Default")
      (node (ref "FB2") (pin "1") (pinfunction "1_1") (pintype "passive"))
      (node (ref "R6") (pin "2") (pinfunction "E2_2") (pintype "passive"))
    )
    (net (code "16") (name "Net-(R10-Pad2)") (class "Default")
      (node (ref "R10") (pin "2") (pinfunction "2_2") (pintype "passive"))
      (node (ref "R8") (pin "1") (pinfunction "1_1") (pintype "passive"))
    )
    (net (code "17") (name "Net-(R16-Pad1)") (class "Default")
      (node (ref "R16") (pin "1") (pinfunction "1_1") (pintype "passive"))
      (node (ref "R9") (pin "2") (pinfunction "2_2") (pintype "passive"))
    )
    (net (code "18") (name "Net-(U1-NRST)") (class "Default")
      (node (ref "C8") (pin "1") (pinfunction "1_1") (pintype "passive"))
      (node (ref "R") (pin "P$1") (pinfunction "P$1_P$1") (pintype "passive"))
      (node (ref "R") (pin "P$2") (pinfunction "P$1_P$2") (pintype "passive"))
      (node (ref "U1") (pin "P$7") (pinfunction "NRST_P$7") (pintype "passive"))
    )
    (net (code "19") (name "Net-(U1-PA11)") (class "Default")
      (node (ref "R1") (pin "2") (pinfunction "2_2") (pintype "passive"))
      (node (ref "U1") (pin "P$32") (pinfunction "PA11_P$32") (pintype "bidirectional"))
    )
    (net (code "20") (name "Net-(U1-PA13)") (class "Default")
      (node (ref "D") (pin "P$1") (pinfunction "P$1_P$1") (pintype "passive"))
      (node (ref "D") (pin "P$2") (pinfunction "P$1_P$2") (pintype "passive"))
      (node (ref "U1") (pin "P$34") (pinfunction "PA13_P$34") (pintype "bidirectional"))
    )
    (net (code "21") (name "Net-(U1-PA14)") (class "Default")
      (node (ref "C") (pin "P$1") (pinfunction "P$1_P$1") (pintype "passive"))
      (node (ref "C") (pin "P$2") (pinfunction "P$1_P$2") (pintype "passive"))
      (node (ref "U1") (pin "P$37") (pinfunction "PA14_P$37") (pintype "bidirectional"))
    )
    (net (code "22") (name "Net-(U1-PF0-OSC_IN)") (class "Default")
      (node (ref "U1") (pin "P$5") (pinfunction "PF0-OSC_IN_P$5") (pintype "bidirectional"))
      (node (ref "X1") (pin "P$1") (pinfunction "1_P$1") (pintype "passive"))
    )
    (net (code "23") (name "Net-(U1-PF1-OSC_OUT)") (class "Default")
      (node (ref "U1") (pin "P$6") (pinfunction "PF1-OSC_OUT_P$6") (pintype "bidirectional"))
      (node (ref "X1") (pin "P$3") (pinfunction "3_P$3") (pintype "passive"))
    )
    (net (code "24") (name "Net-(U1-PF11-OSC_BOOT0)") (class "Default")
      (node (ref "B") (pin "P$1") (pinfunction "P$1_P$1") (pintype "passive"))
      (node (ref "B") (pin "P$2") (pinfunction "P$1_P$2") (pintype "passive"))
      (node (ref "R3") (pin "2") (pinfunction "2_2") (pintype "passive"))
      (node (ref "U1") (pin "P$44") (pinfunction "PF11-OSC_BOOT0_P$44") (pintype "bidirectional"))
    )
    (net (code "25") (name "Net-(U2-IN+)") (class "Default")
      (node (ref "C10") (pin "1") (pinfunction "1_1") (pintype "passive"))
      (node (ref "C11") (pin "2") (pinfunction "2_2") (pintype "passive"))
      (node (ref "R4") (pin "2") (pinfunction "2_2") (pintype "passive"))
      (node (ref "U2") (pin "4") (pinfunction "IN+_4") (pintype "input"))
    )
    (net (code "26") (name "Net-(U2-IN-)") (class "Default")
      (node (ref "C10") (pin "2") (pinfunction "2_2") (pintype "passive"))
      (node (ref "C12") (pin "1") (pinfunction "1_1") (pintype "passive"))
      (node (ref "R5") (pin "2") (pinfunction "2_2") (pintype "passive"))
      (node (ref "U2") (pin "5") (pinfunction "IN-_5") (pintype "input"))
    )
    (net (code "27") (name "Net-(U2-OUT)") (class "Default")
      (node (ref "R7") (pin "1") (pinfunction "1_1") (pintype "passive"))
      (node (ref "U2") (pin "6") (pinfunction "OUT_6") (pintype "output"))
    )
    (net (code "28") (name "Net-(U3-IN+)") (class "Default")
      (node (ref "C16") (pin "1") (pinfunction "1_1") (pintype "passive"))
      (node (ref "C17") (pin "2") (pinfunction "2_2") (pintype "passive"))
      (node (ref "R11") (pin "2") (pinfunction "2_2") (pintype "passive"))
      (node (ref "U3") (pin "4") (pinfunction "IN+_4") (pintype "input"))
    )
    (net (code "29") (name "Net-(U3-IN-)") (class "Default")
      (node (ref "C16") (pin "2") (pinfunction "2_2") (pintype "passive"))
      (node (ref "C18") (pin "1") (pinfunction "1_1") (pintype "passive"))
      (node (ref "R12") (pin "2") (pinfunction "2_2") (pintype "passive"))
      (node (ref "U3") (pin "5") (pinfunction "IN-_5") (pintype "input"))
    )
    (net (code "30") (name "Net-(U3-OUT)") (class "Default")
      (node (ref "R13") (pin "1") (pinfunction "1_1") (pintype "passive"))
      (node (ref "U3") (pin "6") (pinfunction "OUT_6") (pintype "output"))
    )
    (net (code "31") (name "Net-(U4-EN)") (class "Default")
      (node (ref "C22") (pin "1") (pinfunction "1_1") (pintype "passive"))
      (node (ref "R15") (pin "1") (pinfunction "1_1") (pintype "passive"))
      (node (ref "U4") (pin "3") (pinfunction "EN_3") (pintype "input"))
    )
    (net (code "32") (name "PHASE") (class "Default")
      (node (ref "P2") (pin "2") (pinfunction "2_2") (pintype "power_in"))
      (node (ref "R8") (pin "2") (pinfunction "2_2") (pintype "passive"))
    )
    (net (code "33") (name "USART2*_RX") (class "Default")
      (node (ref "P1") (pin "PAD_PD2") (pinfunction "SD2_PAD_PD2") (pintype "bidirectional"))
      (node (ref "U1") (pin "P$13") (pinfunction "PA3_P$13") (pintype "bidirectional"))
    )
    (net (code "34") (name "USART2*_TX") (class "Default")
      (node (ref "P1") (pin "PAD_PU2") (pinfunction "SU2_PAD_PU2") (pintype "bidirectional"))
      (node (ref "U1") (pin "P$12") (pinfunction "PA2_P$12") (pintype "bidirectional"))
    )
    (net (code "35") (name "USART3_RX") (class "Default")
      (node (ref "P1") (pin "PAD_PD4") (pinfunction "SD4_PAD_PD4") (pintype "bidirectional"))
      (node (ref "U1") (pin "P$22") (pinfunction "PB11_P$22") (pintype "bidirectional"))
    )
    (net (code "36") (name "USART3_TX") (class "Default")
      (node (ref "P1") (pin "PAD_PU4") (pinfunction "SU4_PAD_PU4") (pintype "bidirectional"))
      (node (ref "U1") (pin "P$21") (pinfunction "PB10_P$21") (pintype "bidirectional"))
    )
    (net (code "37") (name "USART6_RX") (class "Default")
      (node (ref "P1") (pin "PAD_PD3") (pinfunction "SD3_PAD_PD3") (pintype "bidirectional"))
      (node (ref "U1") (pin "P$15") (pinfunction "PA5_P$15") (pintype "bidirectional"))
    )
    (net (code "38") (name "USART6_TX") (class "Default")
      (node (ref "P1") (pin "PAD_PU3") (pinfunction "SU3_PAD_PU3") (pintype "bidirectional"))
      (node (ref "U1") (pin "P$14") (pinfunction "PA4_P$14") (pintype "bidirectional"))
    )
    (net (code "39") (name "VCC") (class "Default")
      (node (ref "C1") (pin "1") (pinfunction "1_1") (pintype "passive"))
      (node (ref "C14") (pin "1") (pinfunction "1_1") (pintype "passive"))
      (node (ref "C2") (pin "1") (pinfunction "+_1") (pintype "passive"))
      (node (ref "C21") (pin "1") (pinfunction "1_1") (pintype "passive"))
      (node (ref "C24") (pin "1") (pinfunction "+_1") (pintype "passive"))
      (node (ref "FB1") (pin "1") (pinfunction "1_1") (pintype "passive"))
      (node (ref "R15") (pin "2") (pinfunction "2_2") (pintype "passive"))
      (node (ref "U1") (pin "P$9") (pinfunction "VDDA_P$9") (pintype "power_in"))
      (node (ref "U2") (pin "3") (pinfunction "V+_3") (pintype "power_in"))
      (node (ref "U3") (pin "3") (pinfunction "V+_3") (pintype "power_in"))
      (node (ref "U4") (pin "4") (pinfunction "VIN_4") (pintype "power_in"))
    )
    (net (code "40") (name "VDD") (class "Default")
      (node (ref "C3") (pin "1") (pinfunction "1_1") (pintype "passive"))
      (node (ref "C4") (pin "1") (pinfunction "+_1") (pintype "passive"))
      (node (ref "C5") (pin "1") (pinfunction "1_1") (pintype "passive"))
      (node (ref "C6") (pin "1") (pinfunction "1_1") (pintype "passive"))
      (node (ref "C7") (pin "1") (pinfunction "+_1") (pintype "passive"))
      (node (ref "C9") (pin "1") (pinfunction "1_1") (pintype "passive"))
      (node (ref "FB1") (pin "2") (pinfunction "2_2") (pintype "passive"))
      (node (ref "P1") (pin "PAD_PU10") (pinfunction "VDD4_PAD_PU10") (pintype "power_in"))
      (node (ref "P1") (pin "PAD_PU11") (pinfunction "VDD5_PAD_PU11") (pintype "power_in"))
      (node (ref "P1") (pin "PAD_PU8") (pinfunction "VDD2_PAD_PU8") (pintype "power_in"))
      (node (ref "P1") (pin "PAD_PU9") (pinfunction "VDD3_PAD_PU9") (pintype "power_in"))
      (node (ref "U1") (pin "P$1") (pinfunction "VBAT_P$1") (pintype "power_in"))
      (node (ref "U1") (pin "P$24") (pinfunction "VDD_0_P$24") (pintype "power_in"))
      (node (ref "U1") (pin "P$36") (pinfunction "VDDIO2_P$36") (pintype "power_in"))
      (node (ref "U1") (pin "P$48") (pinfunction "VDD_1_P$48") (pintype "power_in"))
    )
    (net (code "41") (name "VOLTAGE_SENSE") (class "Default")
      (node (ref "C19") (pin "1") (pinfunction "1_1") (pintype "passive"))
      (node (ref "R13") (pin "2") (pinfunction "2_2") (pintype "passive"))
      (node (ref "U1") (pin "P$19") (pinfunction "PB1_P$19") (pintype "bidirectional"))
    )
    (net (code "42") (name "VREF") (class "Default")
      (node (ref "U4") (pin "5") (pinfunction "VREF_5") (pintype "power_in"))
    )
    (net (code "43") (name "V_REF") (class "Default")
      (node (ref "C23") (pin "1") (pinfunction "1_1") (pintype "passive"))
      (node (ref "U2") (pin "1") (pinfunction "REF_1") (pintype "input"))
      (node (ref "U3") (pin "1") (pinfunction "REF_1") (pintype "input"))
      (node (ref "U4") (pin "1") (pinfunction "VBIAS_1") (pintype "power_in"))
    )
    (net (code "44") (name "unconnected-(U1-PA0-PadP$10)") (class "Default")
      (node (ref "U1") (pin "P$10") (pinfunction "PA0_P$10") (pintype "bidirectional"))
    )
    (net (code "45") (name "unconnected-(U1-PA1-PadP$11)") (class "Default")
      (node (ref "U1") (pin "P$11") (pinfunction "PA1_P$11") (pintype "bidirectional"))
    )
    (net (code "46") (name "unconnected-(U1-PA6-PadP$16)") (class "Default")
      (node (ref "U1") (pin "P$16") (pinfunction "PA6_P$16") (pintype "bidirectional"))
    )
    (net (code "47") (name "unconnected-(U1-PA8-PadP$29)") (class "Default")
      (node (ref "U1") (pin "P$29") (pinfunction "PA8_P$29") (pintype "bidirectional"))
    )
    (net (code "48") (name "unconnected-(U1-PA9-PadP$30)") (class "Default")
      (node (ref "U1") (pin "P$30") (pinfunction "PA9_P$30") (pintype "bidirectional"))
    )
    (net (code "49") (name "unconnected-(U1-PA10-PadP$31)") (class "Default")
      (node (ref "U1") (pin "P$31") (pinfunction "PA10_P$31") (pintype "bidirectional"))
    )
    (net (code "50") (name "unconnected-(U1-PA12-PadP$33)") (class "Default")
      (node (ref "U1") (pin "P$33") (pinfunction "PA12_P$33") (pintype "bidirectional"))
    )
    (net (code "51") (name "unconnected-(U1-PA15-PadP$38)") (class "Default")
      (node (ref "U1") (pin "P$38") (pinfunction "PA15_P$38") (pintype "bidirectional"))
    )
    (net (code "52") (name "unconnected-(U1-PB3-PadP$39)") (class "Default")
      (node (ref "U1") (pin "P$39") (pinfunction "PB3_P$39") (pintype "bidirectional"))
    )
    (net (code "53") (name "unconnected-(U1-PB4-PadP$40)") (class "Default")
      (node (ref "U1") (pin "P$40") (pinfunction "PB4_P$40") (pintype "bidirectional"))
    )
    (net (code "54") (name "unconnected-(U1-PB5-PadP$41)") (class "Default")
      (node (ref "U1") (pin "P$41") (pinfunction "PB5_P$41") (pintype "bidirectional"))
    )
    (net (code "55") (name "unconnected-(U1-PB6-PadP$42)") (class "Default")
      (node (ref "U1") (pin "P$42") (pinfunction "PB6_P$42") (pintype "bidirectional"))
    )
    (net (code "56") (name "unconnected-(U1-PB7-PadP$43)") (class "Default")
      (node (ref "U1") (pin "P$43") (pinfunction "PB7_P$43") (pintype "bidirectional"))
    )
    (net (code "57") (name "unconnected-(U1-PB8-PadP$45)") (class "Default")
      (node (ref "U1") (pin "P$45") (pinfunction "PB8_P$45") (pintype "bidirectional"))
    )
    (net (code "58") (name "unconnected-(U1-PB9-PadP$46)") (class "Default")
      (node (ref "U1") (pin "P$46") (pinfunction "PB9_P$46") (pintype "bidirectional"))
    )
    (net (code "59") (name "unconnected-(U1-PB12-PadP$25)") (class "Default")
      (node (ref "U1") (pin "P$25") (pinfunction "PB12_P$25") (pintype "bidirectional"))
    )
    (net (code "60") (name "unconnected-(U1-PB13-PadP$26)") (class "Default")
      (node (ref "U1") (pin "P$26") (pinfunction "PB13_P$26") (pintype "bidirectional"))
    )
    (net (code "61") (name "unconnected-(U1-PC15-OSC32_OUT-PadP$4)") (class "Default")
      (node (ref "U1") (pin "P$4") (pinfunction "PC15-OSC32_OUT_P$4") (pintype "bidirectional"))
    )
  )
)
